# RFM69-Gateway-logger.net
KiCad netlist of a schematic drawn in EAGLE
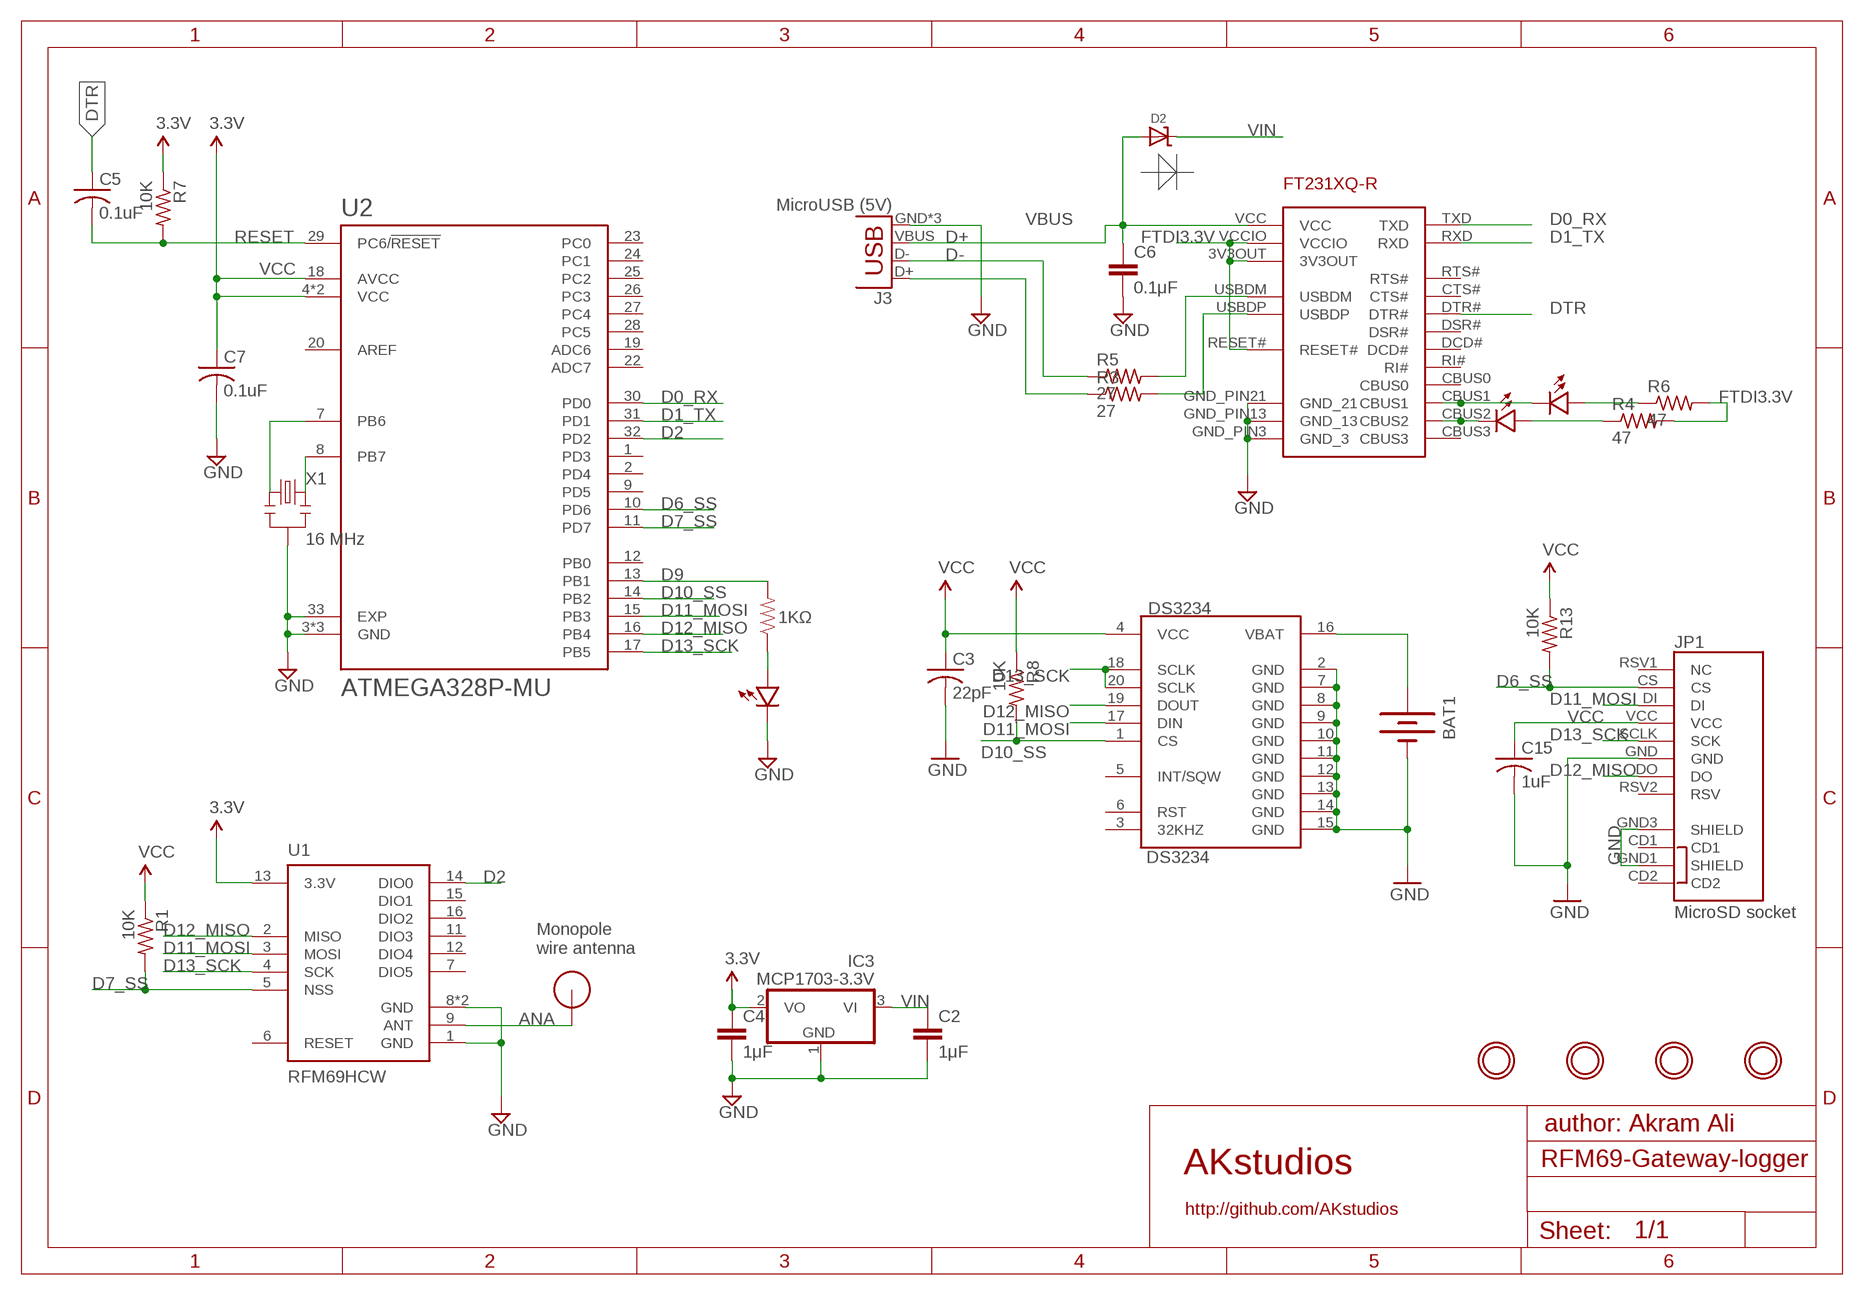
[diagram p0: schematic, sheet 1]

(export (version "E")
  (design (tool "Eeschema 10.0.6"))
  (components
    (comp (ref "BAT1")
      (value "BATTERY12MM")
      (footprint "eagle-import:BATTCON_12MM")
      (fields (field (name "MPN") "3000"))
      (libsource (lib "eagle-import") (part "BATTERY12MM"))
    )
    (comp (ref "C2")
      (value "1μF")
      (footprint "eagle-import:0805")
      (fields (field (name "MPN") "CC0805ZRY5V8BB105"))
      (libsource (lib "eagle-import") (part "SparkFun_CAP0805"))
    )
    (comp (ref "C3")
      (value "22pF")
      (footprint "eagle-import:C0402")
      (libsource (lib "eagle-import") (part "C-USC0402"))
    )
    (comp (ref "C4")
      (value "1μF")
      (footprint "eagle-import:0805")
      (fields (field (name "MPN") "CC0805ZRY5V8BB105"))
      (libsource (lib "eagle-import") (part "CAP0805"))
    )
    (comp (ref "C5")
      (value "0.1uF")
      (footprint "eagle-import:C0402")
      (libsource (lib "eagle-import") (part "C-USC0402"))
    )
    (comp (ref "C6")
      (value "0.1μF")
      (footprint "eagle-import:0805")
      (fields (field (name "MPN") "CC0805KRX7R9BB104"))
      (libsource (lib "eagle-import") (part "SparkFun_CAP0805"))
    )
    (comp (ref "C7")
      (value "0.1uF")
      (footprint "eagle-import:C0402")
      (libsource (lib "eagle-import") (part "C-USC0402"))
    )
    (comp (ref "C15")
      (value "1uF")
      (footprint "eagle-import:C0402")
      (libsource (lib "eagle-import") (part "C-USC0402"))
    )
    (comp (ref "D2")
      (value "MICROBUILDER_DIODE-SCHOTTKYSOD-123")
      (footprint "eagle-import:MICROBUILDER_SOD-123")
      (libsource (lib "eagle-import") (part "MICROBUILDER_DIODE-SCHOTTKYSOD-123"))
    )
    (comp (ref "DS3234")
      (value "DS3234")
      (footprint "eagle-import:DS3234")
      (fields (field (name "MPN") "DS3234S#"))
      (libsource (lib "eagle-import") (part "DS3234"))
    )
    (comp (ref "FT231XQ-R")
      (value "FT231XQ-R")
      (footprint "eagle-import:FTDI_FT231XQ-R_PACKAGE")
      (libsource (lib "eagle-import") (part "FT231XQ-R"))
    )
    (comp (ref "IC3")
      (value "MCP1703-3.3V")
      (footprint "eagle-import:SOT23")
      (fields (field (name "MPN") "MCP1703T-2502E/CB"))
      (libsource (lib "eagle-import") (part "MCP1703CB"))
    )
    (comp (ref "J3")
      (value "MicroUSB (5V)")
      (footprint "eagle-import:USB-MICROB")
      (fields (field (name "MPN") "CONN-09505"))
      (libsource (lib "eagle-import") (part "USB-MICROB"))
    )
    (comp (ref "JP1")
      (value "MicroSD socket")
      (footprint "eagle-import:MICRO-SD-SOCKET-PP")
      (libsource (lib "eagle-import") (part "USD-SOCKETNEW"))
    )
    (comp (ref "R1")
      (value "10K")
      (footprint "eagle-import:R0402")
      (libsource (lib "eagle-import") (part "R-US_R0402"))
    )
    (comp (ref "R2")
      (value "1KΩ")
      (footprint "eagle-import:0805")
      (fields (field (name "MPN") "RC0805FR-071KL"))
      (libsource (lib "eagle-import") (part "RESISTOR0805-RES"))
    )
    (comp (ref "R3")
      (value "27")
      (footprint "eagle-import:R0402")
      (libsource (lib "eagle-import") (part "R-US_R0402"))
    )
    (comp (ref "R4")
      (value "47")
      (footprint "eagle-import:R0402")
      (libsource (lib "eagle-import") (part "R-US_R0402"))
    )
    (comp (ref "R5")
      (value "27")
      (footprint "eagle-import:R0402")
      (libsource (lib "eagle-import") (part "R-US_R0402"))
    )
    (comp (ref "R6")
      (value "47")
      (footprint "eagle-import:R0402")
      (libsource (lib "eagle-import") (part "R-US_R0402"))
    )
    (comp (ref "R7")
      (value "10K")
      (footprint "eagle-import:R0402")
      (libsource (lib "eagle-import") (part "R-US_R0402"))
    )
    (comp (ref "R8")
      (value "10K")
      (footprint "eagle-import:R0402")
      (libsource (lib "eagle-import") (part "R-US_R0402"))
    )
    (comp (ref "R13")
      (value "10K")
      (footprint "eagle-import:R0402")
      (libsource (lib "eagle-import") (part "R-US_R0402"))
    )
    (comp (ref "RX")
      (value "Green")
      (footprint "eagle-import:0805-LED")
      (fields (field (name "MPN") "LG R971-KN-1"))
      (libsource (lib "eagle-import") (part "LED0805"))
    )
    (comp (ref "TX")
      (value "Red")
      (footprint "eagle-import:0805-LED")
      (fields (field (name "MPN") "LG R971-KN-1"))
      (libsource (lib "eagle-import") (part "LED0805"))
    )
    (comp (ref "U$1")
      (value "MOUNTINGHOLE2.0")
      (footprint "eagle-import:MOUNTINGHOLE_2.0_PLATED")
      (libsource (lib "eagle-import") (part "MOUNTINGHOLE2.0"))
    )
    (comp (ref "U$2")
      (value "Status")
      (footprint "eagle-import:0805-LED")
      (fields (field (name "MPN") "LG R971-KN-1"))
      (libsource (lib "eagle-import") (part "LED0805"))
    )
    (comp (ref "U$5")
      (value "MOUNTINGHOLE2.0")
      (footprint "eagle-import:MOUNTINGHOLE_2.0_PLATED")
      (libsource (lib "eagle-import") (part "MOUNTINGHOLE2.0"))
    )
    (comp (ref "U$6")
      (value "RFM12B_ANTENNA")
      (footprint "eagle-import:RFM12B-ANTENNA")
      (libsource (lib "eagle-import") (part "RFM12B_ANTENNA"))
    )
    (comp (ref "U$7")
      (value "MOUNTINGHOLE2.0")
      (footprint "eagle-import:MOUNTINGHOLE_2.0_PLATED")
      (libsource (lib "eagle-import") (part "MOUNTINGHOLE2.0"))
    )
    (comp (ref "U$8")
      (value "MOUNTINGHOLE2.0")
      (footprint "eagle-import:MOUNTINGHOLE_2.0_PLATED")
      (libsource (lib "eagle-import") (part "MOUNTINGHOLE2.0"))
    )
    (comp (ref "U1")
      (value "RFM69HCW")
      (footprint "eagle-import:RFM69HCW-XXXS2")
      (fields (field (name "MPN") "RFM69HW"))
      (libsource (lib "eagle-import") (part "RFM69HCW"))
    )
    (comp (ref "U2")
      (value "ATMEGA328P-MU")
      (footprint "eagle-import:QFN50P500X500X100-33N")
      (fields (field (name "MF") "Atmel") (field (name "MPN") "ATmega328P-MU"))
      (libsource (lib "eagle-import") (part "ATMEGA328P-MU"))
    )
    (comp (ref "X1")
      (value "16 MHz")
      (footprint "eagle-import:RESONATOR-SMD")
      (fields (field (name "MPN") "CSTCE16M0V53-R0"))
      (libsource (lib "eagle-import") (part "RESONATORSMD"))
    )
  )
  (nets
    (net (code "1") (name "/ANA") (class "Default")
      (node (ref "U$6") (pin "P$1") (pinfunction "1_P$1") (pintype "bidirectional"))
      (node (ref "U1") (pin "9") (pinfunction "ANT_9") (pintype "passive"))
    )
    (net (code "2") (name "/D+") (class "Default")
      (node (ref "J3") (pin "D+") (pinfunction "D+_D+") (pintype "bidirectional"))
      (node (ref "R3") (pin "1") (pinfunction "1_1") (pintype "passive"))
    )
    (net (code "3") (name "/D-") (class "Default")
      (node (ref "J3") (pin "D-") (pinfunction "D-_D-") (pintype "bidirectional"))
      (node (ref "R5") (pin "1") (pinfunction "1_1") (pintype "passive"))
    )
    (net (code "4") (name "/D0_RX") (class "Default")
      (node (ref "FT231XQ-R") (pin "TXD") (pinfunction "TXD_TXD") (pintype "bidirectional"))
      (node (ref "U2") (pin "30") (pinfunction "PD0_30") (pintype "bidirectional"))
    )
    (net (code "5") (name "/D1_TX") (class "Default")
      (node (ref "FT231XQ-R") (pin "RXD") (pinfunction "RXD_RXD") (pintype "bidirectional"))
      (node (ref "U2") (pin "31") (pinfunction "PD1_31") (pintype "bidirectional"))
    )
    (net (code "6") (name "/D2") (class "Default")
      (node (ref "U1") (pin "14") (pinfunction "DIO0_14") (pintype "bidirectional"))
      (node (ref "U2") (pin "32") (pinfunction "PD2_32") (pintype "bidirectional"))
    )
    (net (code "7") (name "/D6_SS") (class "Default")
      (node (ref "JP1") (pin "CS") (pinfunction "CS_CS") (pintype "bidirectional"))
      (node (ref "R13") (pin "2") (pinfunction "2_2") (pintype "passive"))
      (node (ref "U2") (pin "10") (pinfunction "PD6_10") (pintype "bidirectional"))
    )
    (net (code "8") (name "/D7_SS") (class "Default")
      (node (ref "R1") (pin "2") (pinfunction "2_2") (pintype "passive"))
      (node (ref "U1") (pin "5") (pinfunction "NSS_5") (pintype "input"))
      (node (ref "U2") (pin "11") (pinfunction "PD7_11") (pintype "bidirectional"))
    )
    (net (code "9") (name "/D9") (class "Default")
      (node (ref "R2") (pin "2") (pinfunction "2_2") (pintype "passive"))
      (node (ref "U2") (pin "13") (pinfunction "PB1_13") (pintype "bidirectional"))
    )
    (net (code "10") (name "/D10_SS") (class "Default")
      (node (ref "DS3234") (pin "1") (pinfunction "CS_1") (pintype "bidirectional"))
      (node (ref "R8") (pin "2") (pinfunction "2_2") (pintype "passive"))
      (node (ref "U2") (pin "14") (pinfunction "PB2_14") (pintype "bidirectional"))
    )
    (net (code "11") (name "/D11_MOSI") (class "Default")
      (node (ref "DS3234") (pin "17") (pinfunction "DIN_17") (pintype "bidirectional"))
      (node (ref "JP1") (pin "DI") (pinfunction "DI_DI") (pintype "bidirectional"))
      (node (ref "U1") (pin "3") (pinfunction "MOSI_3") (pintype "input"))
      (node (ref "U2") (pin "15") (pinfunction "PB3_15") (pintype "bidirectional"))
    )
    (net (code "12") (name "/D12_MISO") (class "Default")
      (node (ref "DS3234") (pin "19") (pinfunction "DOUT_19") (pintype "bidirectional"))
      (node (ref "JP1") (pin "DO") (pinfunction "DO_DO") (pintype "bidirectional"))
      (node (ref "U1") (pin "2") (pinfunction "MISO_2") (pintype "bidirectional"))
      (node (ref "U2") (pin "16") (pinfunction "PB4_16") (pintype "bidirectional"))
    )
    (net (code "13") (name "/D13_SCK") (class "Default")
      (node (ref "DS3234") (pin "18") (pinfunction "SCLK_18") (pintype "bidirectional"))
      (node (ref "DS3234") (pin "20") (pinfunction "SCLK_20") (pintype "bidirectional"))
      (node (ref "JP1") (pin "SCLK") (pinfunction "SCK_SCLK") (pintype "bidirectional"))
      (node (ref "U1") (pin "4") (pinfunction "SCK_4") (pintype "input"))
      (node (ref "U2") (pin "17") (pinfunction "PB5_17") (pintype "bidirectional"))
    )
    (net (code "14") (name "/FTDI3.3V") (class "Default")
      (node (ref "FT231XQ-R") (pin "3V3OUT") (pinfunction "3V3OUT_3V3OUT") (pintype "bidirectional"))
      (node (ref "FT231XQ-R") (pin "RESET#") (pinfunction "RESET#_RESET#") (pintype "bidirectional"))
      (node (ref "FT231XQ-R") (pin "VCCIO") (pinfunction "VCCIO_VCCIO") (pintype "bidirectional"))
      (node (ref "R4") (pin "2") (pinfunction "2_2") (pintype "passive"))
      (node (ref "R6") (pin "2") (pinfunction "2_2") (pintype "passive"))
    )
    (net (code "15") (name "/RESET") (class "Default")
      (node (ref "C5") (pin "2") (pinfunction "2_2") (pintype "passive"))
      (node (ref "R7") (pin "2") (pinfunction "2_2") (pintype "passive"))
      (node (ref "U2") (pin "29") (pinfunction "PC6/~{RESET}_29") (pintype "bidirectional"))
    )
    (net (code "16") (name "/VBUS") (class "Default")
      (node (ref "C6") (pin "1") (pinfunction "1_1") (pintype "passive"))
      (node (ref "D2") (pin "A") (pinfunction "A_A") (pintype "passive"))
      (node (ref "FT231XQ-R") (pin "VCC") (pinfunction "VCC_VCC") (pintype "bidirectional"))
      (node (ref "J3") (pin "VBUS") (pinfunction "VBUS_VBUS") (pintype "bidirectional"))
    )
    (net (code "17") (name "/VIN") (class "Default")
      (node (ref "C2") (pin "1") (pinfunction "1_1") (pintype "passive"))
      (node (ref "D2") (pin "C") (pinfunction "C_C") (pintype "passive"))
      (node (ref "IC3") (pin "3") (pinfunction "VI_3") (pintype "input"))
    )
    (net (code "18") (name "3.3V") (class "Default")
      (node (ref "C15") (pin "1") (pinfunction "1_1") (pintype "passive"))
      (node (ref "C3") (pin "1") (pinfunction "1_1") (pintype "passive"))
      (node (ref "C4") (pin "1") (pinfunction "1_1") (pintype "passive"))
      (node (ref "C7") (pin "1") (pinfunction "1_1") (pintype "passive"))
      (node (ref "DS3234") (pin "4") (pinfunction "VCC_4") (pintype "bidirectional"))
      (node (ref "IC3") (pin "2") (pinfunction "VO_2") (pintype "passive"))
      (node (ref "JP1") (pin "VCC") (pinfunction "VCC_VCC") (pintype "bidirectional"))
      (node (ref "R1") (pin "1") (pinfunction "1_1") (pintype "passive"))
      (node (ref "R13") (pin "1") (pinfunction "1_1") (pintype "passive"))
      (node (ref "R7") (pin "1") (pinfunction "1_1") (pintype "passive"))
      (node (ref "R8") (pin "1") (pinfunction "1_1") (pintype "passive"))
      (node (ref "U1") (pin "13") (pinfunction "3.3V_13") (pintype "power_in"))
      (node (ref "U2") (pin "18") (pinfunction "AVCC_18") (pintype "power_in"))
      (node (ref "U2") (pin "4") (pinfunction "VCC_4") (pintype "power_in"))
      (node (ref "U2") (pin "6") (pinfunction "VCC_6") (pintype "power_in"))
    )
    (net (code "19") (name "DTR") (class "Default")
      (node (ref "C5") (pin "1") (pinfunction "1_1") (pintype "passive"))
      (node (ref "FT231XQ-R") (pin "DTR#") (pinfunction "DTR#_DTR#") (pintype "bidirectional"))
    )
    (net (code "20") (name "GND") (class "Default")
      (node (ref "BAT1") (pin "GND") (pinfunction "-_GND") (pintype "power_in"))
      (node (ref "C15") (pin "2") (pinfunction "2_2") (pintype "passive"))
      (node (ref "C2") (pin "2") (pinfunction "2_2") (pintype "passive"))
      (node (ref "C3") (pin "2") (pinfunction "2_2") (pintype "passive"))
      (node (ref "C4") (pin "2") (pinfunction "2_2") (pintype "passive"))
      (node (ref "C6") (pin "2") (pinfunction "2_2") (pintype "passive"))
      (node (ref "C7") (pin "2") (pinfunction "2_2") (pintype "passive"))
      (node (ref "DS3234") (pin "10") (pinfunction "GND_10") (pintype "bidirectional"))
      (node (ref "DS3234") (pin "11") (pinfunction "GND_11") (pintype "bidirectional"))
      (node (ref "DS3234") (pin "12") (pinfunction "GND_12") (pintype "bidirectional"))
      (node (ref "DS3234") (pin "13") (pinfunction "GND_13") (pintype "bidirectional"))
      (node (ref "DS3234") (pin "14") (pinfunction "GND_14") (pintype "bidirectional"))
      (node (ref "DS3234") (pin "15") (pinfunction "GND_15") (pintype "bidirectional"))
      (node (ref "DS3234") (pin "2") (pinfunction "GND_2") (pintype "bidirectional"))
      (node (ref "DS3234") (pin "7") (pinfunction "GND_7") (pintype "bidirectional"))
      (node (ref "DS3234") (pin "8") (pinfunction "GND_8") (pintype "bidirectional"))
      (node (ref "DS3234") (pin "9") (pinfunction "GND_9") (pintype "bidirectional"))
      (node (ref "FT231XQ-R") (pin "GND_PIN13") (pinfunction "GND_13_GND_PIN13") (pintype "bidirectional"))
      (node (ref "FT231XQ-R") (pin "GND_PIN21") (pinfunction "GND_21_GND_PIN21") (pintype "bidirectional"))
      (node (ref "FT231XQ-R") (pin "GND_PIN3") (pinfunction "GND_3_GND_PIN3") (pintype "bidirectional"))
      (node (ref "IC3") (pin "1") (pinfunction "GND_1") (pintype "passive"))
      (node (ref "J3") (pin "GND") (pinfunction "GND_GND") (pintype "bidirectional"))
      (node (ref "J3") (pin "MT1") (pinfunction "GND_MT1") (pintype "bidirectional"))
      (node (ref "J3") (pin "MT2") (pinfunction "GND_MT2") (pintype "bidirectional"))
      (node (ref "JP1") (pin "GND") (pinfunction "GND_GND") (pintype "bidirectional"))
      (node (ref "JP1") (pin "GND1") (pinfunction "SHIELD_GND1") (pintype "bidirectional"))
      (node (ref "JP1") (pin "GND3") (pinfunction "SHIELD_GND3") (pintype "bidirectional"))
      (node (ref "U$2") (pin "MINUS") (pinfunction "MINUS_MINUS") (pintype "passive"))
      (node (ref "U1") (pin "1") (pinfunction "GND_1") (pintype "power_in"))
      (node (ref "U1") (pin "10") (pinfunction "GND_10") (pintype "power_in"))
      (node (ref "U1") (pin "8") (pinfunction "GND_8") (pintype "power_in"))
      (node (ref "U2") (pin "21") (pinfunction "GND_21") (pintype "power_in"))
      (node (ref "U2") (pin "3") (pinfunction "GND_3") (pintype "power_in"))
      (node (ref "U2") (pin "33") (pinfunction "EXP_33") (pintype "power_in"))
      (node (ref "U2") (pin "5") (pinfunction "GND_5") (pintype "power_in"))
      (node (ref "X1") (pin "2") (pinfunction "2_2") (pintype "passive"))
    )
    (net (code "21") (name "Net-(BAT1-+)") (class "Default")
      (node (ref "BAT1") (pin "PWR@1") (pinfunction "+_PWR@1") (pintype "power_in"))
      (node (ref "DS3234") (pin "16") (pinfunction "VBAT_16") (pintype "bidirectional"))
    )
    (net (code "22") (name "Net-(FT231XQ-R-PadCBUS1)") (class "Default")
      (node (ref "FT231XQ-R") (pin "CBUS1") (pinfunction "CBUS1_CBUS1") (pintype "bidirectional"))
      (node (ref "RX") (pin "MINUS") (pinfunction "MINUS_MINUS") (pintype "passive"))
    )
    (net (code "23") (name "Net-(FT231XQ-R-PadCBUS2)") (class "Default")
      (node (ref "FT231XQ-R") (pin "CBUS2") (pinfunction "CBUS2_CBUS2") (pintype "bidirectional"))
      (node (ref "TX") (pin "MINUS") (pinfunction "MINUS_MINUS") (pintype "passive"))
    )
    (net (code "24") (name "Net-(FT231XQ-R-PadUSBDM)") (class "Default")
      (node (ref "FT231XQ-R") (pin "USBDM") (pinfunction "USBDM_USBDM") (pintype "bidirectional"))
      (node (ref "R5") (pin "2") (pinfunction "2_2") (pintype "passive"))
    )
    (net (code "25") (name "Net-(FT231XQ-R-PadUSBDP)") (class "Default")
      (node (ref "FT231XQ-R") (pin "USBDP") (pinfunction "USBDP_USBDP") (pintype "bidirectional"))
      (node (ref "R3") (pin "2") (pinfunction "2_2") (pintype "passive"))
    )
    (net (code "26") (name "Net-(R2-Pad1)") (class "Default")
      (node (ref "R2") (pin "1") (pinfunction "1_1") (pintype "passive"))
      (node (ref "U$2") (pin "PLUS") (pinfunction "PLUS_PLUS") (pintype "passive"))
    )
    (net (code "27") (name "Net-(R4-Pad1)") (class "Default")
      (node (ref "R4") (pin "1") (pinfunction "1_1") (pintype "passive"))
      (node (ref "TX") (pin "PLUS") (pinfunction "PLUS_PLUS") (pintype "passive"))
    )
    (net (code "28") (name "Net-(R6-Pad1)") (class "Default")
      (node (ref "R6") (pin "1") (pinfunction "1_1") (pintype "passive"))
      (node (ref "RX") (pin "PLUS") (pinfunction "PLUS_PLUS") (pintype "passive"))
    )
    (net (code "29") (name "Net-(U2-PB6)") (class "Default")
      (node (ref "U2") (pin "7") (pinfunction "PB6_7") (pintype "bidirectional"))
      (node (ref "X1") (pin "1") (pinfunction "1_1") (pintype "passive"))
    )
    (net (code "30") (name "Net-(U2-PB7)") (class "Default")
      (node (ref "U2") (pin "8") (pinfunction "PB7_8") (pintype "bidirectional"))
      (node (ref "X1") (pin "3") (pinfunction "3_3") (pintype "passive"))
    )
    (net (code "31") (name "unconnected-(DS3234-32KHZ-Pad3)") (class "Default")
      (node (ref "DS3234") (pin "3") (pinfunction "32KHZ_3") (pintype "bidirectional"))
    )
    (net (code "32") (name "unconnected-(DS3234-INT{slash}SQW-Pad5)") (class "Default")
      (node (ref "DS3234") (pin "5") (pinfunction "INT/SQW_5") (pintype "bidirectional"))
    )
    (net (code "33") (name "unconnected-(DS3234-RST-Pad6)") (class "Default")
      (node (ref "DS3234") (pin "6") (pinfunction "RST_6") (pintype "bidirectional"))
    )
    (net (code "34") (name "unconnected-(FT231XQ-R-PadCBUS0)") (class "Default")
      (node (ref "FT231XQ-R") (pin "CBUS0") (pinfunction "CBUS0_CBUS0") (pintype "bidirectional"))
    )
    (net (code "35") (name "unconnected-(FT231XQ-R-PadCBUS3)") (class "Default")
      (node (ref "FT231XQ-R") (pin "CBUS3") (pinfunction "CBUS3_CBUS3") (pintype "bidirectional"))
    )
    (net (code "36") (name "unconnected-(FT231XQ-R-PadCTS#)") (class "Default")
      (node (ref "FT231XQ-R") (pin "CTS#") (pinfunction "CTS#_CTS#") (pintype "bidirectional"))
    )
    (net (code "37") (name "unconnected-(FT231XQ-R-PadDCD#)") (class "Default")
      (node (ref "FT231XQ-R") (pin "DCD#") (pinfunction "DCD#_DCD#") (pintype "bidirectional"))
    )
    (net (code "38") (name "unconnected-(FT231XQ-R-PadDSR#)") (class "Default")
      (node (ref "FT231XQ-R") (pin "DSR#") (pinfunction "DSR#_DSR#") (pintype "bidirectional"))
    )
    (net (code "39") (name "unconnected-(FT231XQ-R-PadRI#)") (class "Default")
      (node (ref "FT231XQ-R") (pin "RI#") (pinfunction "RI#_RI#") (pintype "bidirectional"))
    )
    (net (code "40") (name "unconnected-(FT231XQ-R-PadRTS#)") (class "Default")
      (node (ref "FT231XQ-R") (pin "RTS#") (pinfunction "RTS#_RTS#") (pintype "bidirectional"))
    )
    (net (code "41") (name "unconnected-(JP1-NC-PadRSV1)") (class "Default")
      (node (ref "JP1") (pin "RSV1") (pinfunction "NC_RSV1") (pintype "bidirectional"))
    )
    (net (code "42") (name "unconnected-(JP1-PadCD1)") (class "Default")
      (node (ref "JP1") (pin "CD1") (pinfunction "CD1_CD1") (pintype "bidirectional"))
    )
    (net (code "43") (name "unconnected-(JP1-PadCD2)") (class "Default")
      (node (ref "JP1") (pin "CD2") (pinfunction "CD2_CD2") (pintype "bidirectional"))
    )
    (net (code "44") (name "unconnected-(JP1-RSV-PadRSV2)") (class "Default")
      (node (ref "JP1") (pin "RSV2") (pinfunction "RSV_RSV2") (pintype "bidirectional"))
    )
    (net (code "45") (name "unconnected-(U1-DIO1-Pad15)") (class "Default")
      (node (ref "U1") (pin "15") (pinfunction "DIO1_15") (pintype "bidirectional"))
    )
    (net (code "46") (name "unconnected-(U1-DIO2-Pad16)") (class "Default")
      (node (ref "U1") (pin "16") (pinfunction "DIO2_16") (pintype "bidirectional"))
    )
    (net (code "47") (name "unconnected-(U1-DIO3-Pad11)") (class "Default")
      (node (ref "U1") (pin "11") (pinfunction "DIO3_11") (pintype "bidirectional"))
    )
    (net (code "48") (name "unconnected-(U1-DIO4-Pad12)") (class "Default")
      (node (ref "U1") (pin "12") (pinfunction "DIO4_12") (pintype "bidirectional"))
    )
    (net (code "49") (name "unconnected-(U1-DIO5-Pad7)") (class "Default")
      (node (ref "U1") (pin "7") (pinfunction "DIO5_7") (pintype "bidirectional"))
    )
    (net (code "50") (name "unconnected-(U1-RESET-Pad6)") (class "Default")
      (node (ref "U1") (pin "6") (pinfunction "RESET_6") (pintype "input"))
    )
    (net (code "51") (name "unconnected-(U2-ADC6-Pad19)") (class "Default")
      (node (ref "U2") (pin "19") (pinfunction "ADC6_19") (pintype "bidirectional"))
    )
    (net (code "52") (name "unconnected-(U2-ADC7-Pad22)") (class "Default")
      (node (ref "U2") (pin "22") (pinfunction "ADC7_22") (pintype "bidirectional"))
    )
    (net (code "53") (name "unconnected-(U2-AREF-Pad20)") (class "Default")
      (node (ref "U2") (pin "20") (pinfunction "AREF_20") (pintype "input"))
    )
    (net (code "54") (name "unconnected-(U2-PB0-Pad12)") (class "Default")
      (node (ref "U2") (pin "12") (pinfunction "PB0_12") (pintype "bidirectional"))
    )
    (net (code "55") (name "unconnected-(U2-PC0-Pad23)") (class "Default")
      (node (ref "U2") (pin "23") (pinfunction "PC0_23") (pintype "bidirectional"))
    )
    (net (code "56") (name "unconnected-(U2-PC1-Pad24)") (class "Default")
      (node (ref "U2") (pin "24") (pinfunction "PC1_24") (pintype "bidirectional"))
    )
    (net (code "57") (name "unconnected-(U2-PC2-Pad25)") (class "Default")
      (node (ref "U2") (pin "25") (pinfunction "PC2_25") (pintype "bidirectional"))
    )
    (net (code "58") (name "unconnected-(U2-PC3-Pad26)") (class "Default")
      (node (ref "U2") (pin "26") (pinfunction "PC3_26") (pintype "bidirectional"))
    )
    (net (code "59") (name "unconnected-(U2-PC4-Pad27)") (class "Default")
      (node (ref "U2") (pin "27") (pinfunction "PC4_27") (pintype "bidirectional"))
    )
    (net (code "60") (name "unconnected-(U2-PC5-Pad28)") (class "Default")
      (node (ref "U2") (pin "28") (pinfunction "PC5_28") (pintype "bidirectional"))
    )
    (net (code "61") (name "unconnected-(U2-PD3-Pad1)") (class "Default")
      (node (ref "U2") (pin "1") (pinfunction "PD3_1") (pintype "bidirectional"))
    )
    (net (code "62") (name "unconnected-(U2-PD4-Pad2)") (class "Default")
      (node (ref "U2") (pin "2") (pinfunction "PD4_2") (pintype "bidirectional"))
    )
    (net (code "63") (name "unconnected-(U2-PD5-Pad9)") (class "Default")
      (node (ref "U2") (pin "9") (pinfunction "PD5_9") (pintype "bidirectional"))
    )
  )
)
